# EveryCook_RaspiShield_V3.net
KiCad netlist of a schematic drawn in EAGLE
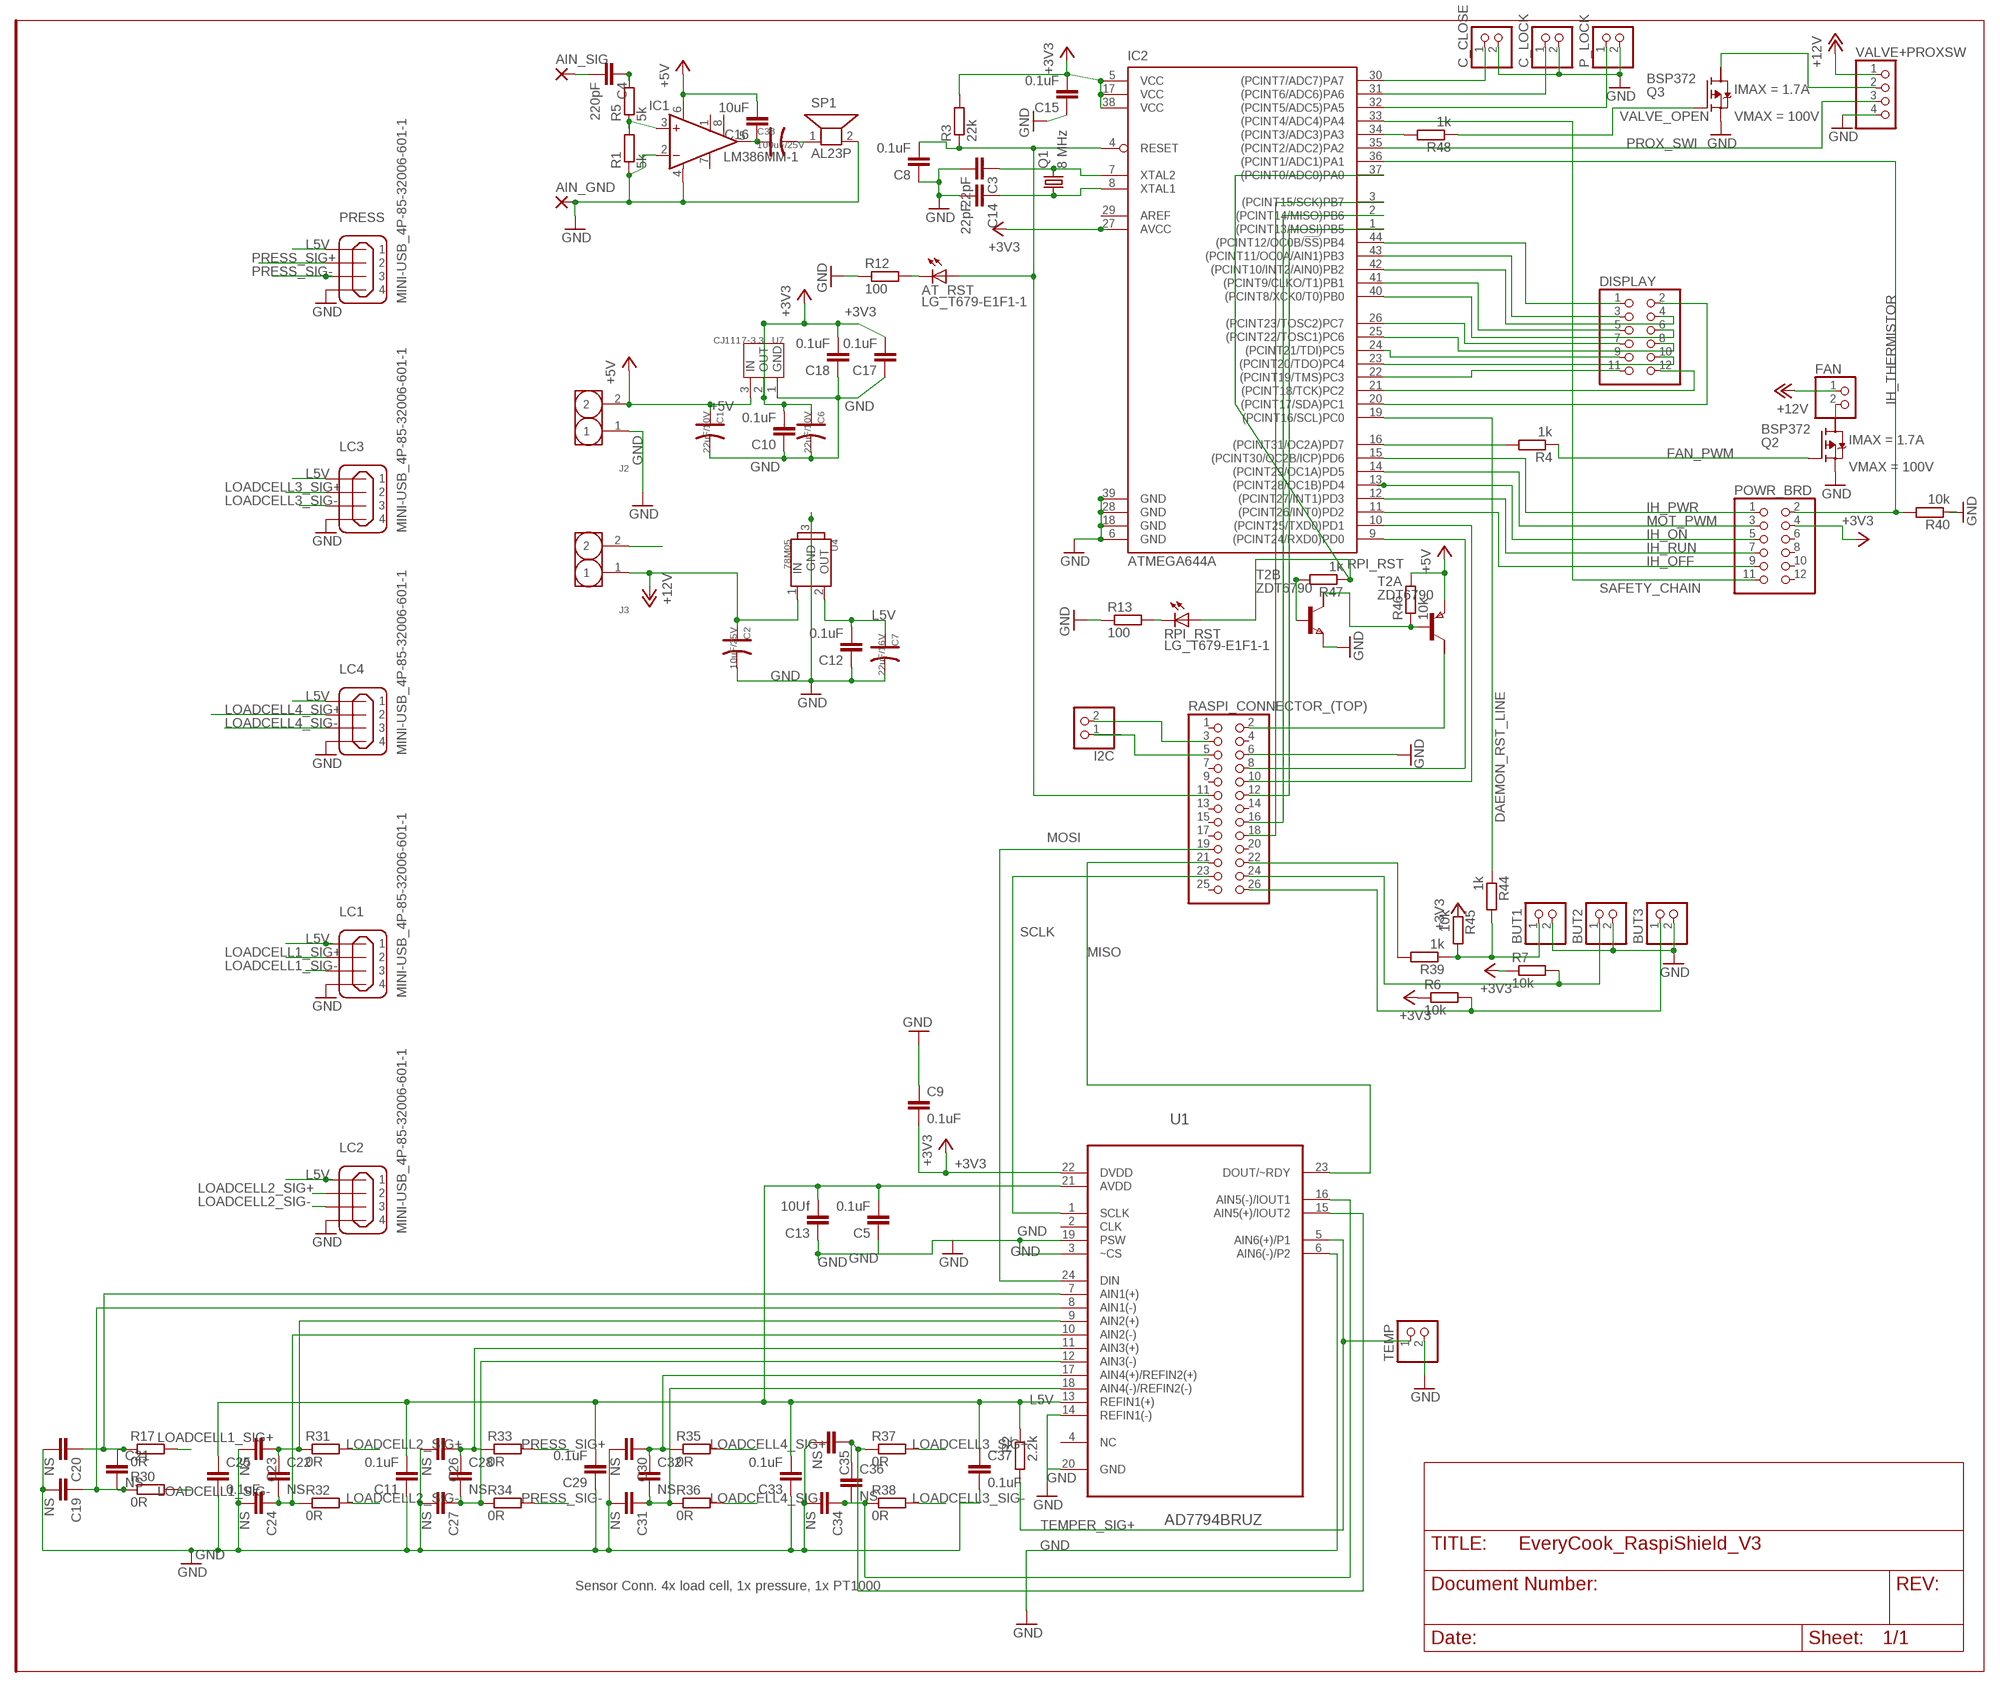
[diagram p0: schematic, sheet 1]

(export (version "E")
  (design (tool "Eeschema 10.0.6"))
  (components
    (comp (ref "AIN_GND")
      (value "2,15/1,0")
      (footprint "eagle-import:2,15_1,0")
      (libsource (lib "eagle-import") (part "2,15/1,0"))
    )
    (comp (ref "AIN_SIG")
      (value "2,15/1,0")
      (footprint "eagle-import:2,15_1,0")
      (libsource (lib "eagle-import") (part "2,15/1,0"))
    )
    (comp (ref "AT_RST")
      (value "LG_T679-E1F1-1")
      (footprint "eagle-import:PLCC2")
      (libsource (lib "eagle-import") (part "_T679-?-1E1F1LG"))
    )
    (comp (ref "BUT1")
      (value "PINHD-1X2")
      (footprint "eagle-import:1X02")
      (libsource (lib "eagle-import") (part "PINHD-1X2"))
    )
    (comp (ref "BUT2")
      (value "PINHD-1X2")
      (footprint "eagle-import:1X02")
      (libsource (lib "eagle-import") (part "PINHD-1X2"))
    )
    (comp (ref "BUT3")
      (value "PINHD-1X2")
      (footprint "eagle-import:1X02")
      (libsource (lib "eagle-import") (part "PINHD-1X2"))
    )
    (comp (ref "C1")
      (value "22uF/10V")
      (footprint "eagle-import:AVX-A")
      (libsource (lib "eagle-import") (part "CAP-AVX-A"))
    )
    (comp (ref "C2")
      (value "10uF/25V")
      (footprint "eagle-import:ELECTRO-SMD-B-4.8MM")
      (libsource (lib "eagle-import") (part "CAP-ELECTRO-B"))
    )
    (comp (ref "C3")
      (value "22pF")
      (footprint "eagle-import:C0805")
      (libsource (lib "eagle-import") (part "C-EUC0805"))
    )
    (comp (ref "C4")
      (value "220pF")
      (footprint "eagle-import:C0805")
      (libsource (lib "eagle-import") (part "C-EUC0805"))
    )
    (comp (ref "C5")
      (value "0.1uF")
      (footprint "eagle-import:C0805")
      (libsource (lib "eagle-import") (part "C-EUC0805"))
    )
    (comp (ref "C6")
      (value "22uF/10V")
      (footprint "eagle-import:AVX-A")
      (libsource (lib "eagle-import") (part "CAP-AVX-A"))
    )
    (comp (ref "C7")
      (value "22uF/16V")
      (footprint "eagle-import:ELECTRO-SMD-B-4.8MM")
      (libsource (lib "eagle-import") (part "CAP-ELECTRO-B"))
    )
    (comp (ref "C8")
      (value "0.1uF")
      (footprint "eagle-import:C0805")
      (libsource (lib "eagle-import") (part "C-EUC0805"))
    )
    (comp (ref "C9")
      (value "0.1uF")
      (footprint "eagle-import:C0805")
      (libsource (lib "eagle-import") (part "C-EUC0805"))
    )
    (comp (ref "C10")
      (value "0.1uF")
      (footprint "eagle-import:C0805")
      (libsource (lib "eagle-import") (part "C-EUC0805"))
    )
    (comp (ref "C11")
      (value "0.1uF")
      (footprint "eagle-import:C0805")
      (libsource (lib "eagle-import") (part "C-EUC0805"))
    )
    (comp (ref "C12")
      (value "0.1uF")
      (footprint "eagle-import:C0805")
      (libsource (lib "eagle-import") (part "C-EUC0805"))
    )
    (comp (ref "C13")
      (value "10Uf")
      (footprint "eagle-import:C0805")
      (libsource (lib "eagle-import") (part "C-EUC0805"))
    )
    (comp (ref "C14")
      (value "22pF")
      (footprint "eagle-import:C0805")
      (libsource (lib "eagle-import") (part "C-EUC0805"))
    )
    (comp (ref "C15")
      (value "0.1uF")
      (footprint "eagle-import:C0805")
      (libsource (lib "eagle-import") (part "C-EUC0805"))
    )
    (comp (ref "C16")
      (value "10uF")
      (footprint "eagle-import:C0805")
      (libsource (lib "eagle-import") (part "C-EUC0805"))
    )
    (comp (ref "C17")
      (value "0.1uF")
      (footprint "eagle-import:C0805")
      (libsource (lib "eagle-import") (part "C-EUC0805"))
    )
    (comp (ref "C18")
      (value "0.1uF")
      (footprint "eagle-import:C0805")
      (libsource (lib "eagle-import") (part "C-EUC0805"))
    )
    (comp (ref "C19")
      (value "NS")
      (footprint "eagle-import:C0805")
      (libsource (lib "eagle-import") (part "C-EUC0805"))
    )
    (comp (ref "C20")
      (value "NS")
      (footprint "eagle-import:C0805")
      (libsource (lib "eagle-import") (part "C-EUC0805"))
    )
    (comp (ref "C21")
      (value "NS")
      (footprint "eagle-import:C0805")
      (libsource (lib "eagle-import") (part "C-EUC0805"))
    )
    (comp (ref "C22")
      (value "NS")
      (footprint "eagle-import:C0805")
      (libsource (lib "eagle-import") (part "C-EUC0805"))
    )
    (comp (ref "C23")
      (value "NS")
      (footprint "eagle-import:C0805")
      (libsource (lib "eagle-import") (part "C-EUC0805"))
    )
    (comp (ref "C24")
      (value "NS")
      (footprint "eagle-import:C0805")
      (libsource (lib "eagle-import") (part "C-EUC0805"))
    )
    (comp (ref "C25")
      (value "0.1uF")
      (footprint "eagle-import:C0805")
      (libsource (lib "eagle-import") (part "C-EUC0805"))
    )
    (comp (ref "C26")
      (value "NS")
      (footprint "eagle-import:C0805")
      (libsource (lib "eagle-import") (part "C-EUC0805"))
    )
    (comp (ref "C27")
      (value "NS")
      (footprint "eagle-import:C0805")
      (libsource (lib "eagle-import") (part "C-EUC0805"))
    )
    (comp (ref "C28")
      (value "NS")
      (footprint "eagle-import:C0805")
      (libsource (lib "eagle-import") (part "C-EUC0805"))
    )
    (comp (ref "C29")
      (value "0.1uF")
      (footprint "eagle-import:C0805")
      (libsource (lib "eagle-import") (part "C-EUC0805"))
    )
    (comp (ref "C30")
      (value "NS")
      (footprint "eagle-import:C0805")
      (libsource (lib "eagle-import") (part "C-EUC0805"))
    )
    (comp (ref "C31")
      (value "NS")
      (footprint "eagle-import:C0805")
      (libsource (lib "eagle-import") (part "C-EUC0805"))
    )
    (comp (ref "C32")
      (value "NS")
      (footprint "eagle-import:C0805")
      (libsource (lib "eagle-import") (part "C-EUC0805"))
    )
    (comp (ref "C33")
      (value "0.1uF")
      (footprint "eagle-import:C0805")
      (libsource (lib "eagle-import") (part "C-EUC0805"))
    )
    (comp (ref "C34")
      (value "NS")
      (footprint "eagle-import:C0805")
      (libsource (lib "eagle-import") (part "C-EUC0805"))
    )
    (comp (ref "C35")
      (value "NS")
      (footprint "eagle-import:C0805")
      (libsource (lib "eagle-import") (part "C-EUC0805"))
    )
    (comp (ref "C36")
      (value "NS")
      (footprint "eagle-import:C0805")
      (libsource (lib "eagle-import") (part "C-EUC0805"))
    )
    (comp (ref "C37")
      (value "0.1uF")
      (footprint "eagle-import:C0805")
      (libsource (lib "eagle-import") (part "C-EUC0805"))
    )
    (comp (ref "C38")
      (value "100uF/25V")
      (footprint "eagle-import:ELECTRO-SMD-B-4.8MM")
      (libsource (lib "eagle-import") (part "CAP-ELECTRO-B"))
    )
    (comp (ref "C_CLOSE")
      (value "PINHD-1X2")
      (footprint "eagle-import:1X02")
      (libsource (lib "eagle-import") (part "PINHD-1X2"))
    )
    (comp (ref "C_LOCK")
      (value "PINHD-1X2")
      (footprint "eagle-import:1X02")
      (libsource (lib "eagle-import") (part "PINHD-1X2"))
    )
    (comp (ref "DISPLAY")
      (value "PINHD-2X6")
      (footprint "eagle-import:2X06")
      (libsource (lib "eagle-import") (part "PINHD-2X6"))
    )
    (comp (ref "FAN")
      (value "PINHD-1X2")
      (footprint "eagle-import:1X02")
      (libsource (lib "eagle-import") (part "PINHD-1X2"))
    )
    (comp (ref "I2C")
      (value "PINHD-1X2")
      (footprint "eagle-import:1X02")
      (libsource (lib "eagle-import") (part "PINHD-1X2"))
    )
    (comp (ref "IC1")
      (value "LM386MM-1")
      (footprint "eagle-import:MMSOP08")
      (libsource (lib "eagle-import") (part "LM386?-MM1"))
    )
    (comp (ref "IC2")
      (value "ATMEGA644A")
      (footprint "eagle-import:TQFP44")
      (fields (field (name "MPN") "ATMEGA644PV-10AU"))
      (libsource (lib "eagle-import") (part "ATMEGA644A"))
    )
    (comp (ref "J2")
      (value "HEADER-2P-5.0")
      (footprint "eagle-import:2P-5.0")
      (libsource (lib "eagle-import") (part "HEADER-2P-5.0"))
    )
    (comp (ref "J3")
      (value "HEADER-2P-5.0")
      (footprint "eagle-import:2P-5.0")
      (libsource (lib "eagle-import") (part "HEADER-2P-5.0"))
    )
    (comp (ref "LC1")
      (value "MINI-USB_4P-85-32006-601-1")
      (footprint "eagle-import:85-32006-601-1")
      (libsource (lib "eagle-import") (part "MINI-USB_4P-85-32006-601-1"))
    )
    (comp (ref "LC2")
      (value "MINI-USB_4P-85-32006-601-1")
      (footprint "eagle-import:85-32006-601-1")
      (libsource (lib "eagle-import") (part "MINI-USB_4P-85-32006-601-1"))
    )
    (comp (ref "LC3")
      (value "MINI-USB_4P-85-32006-601-1")
      (footprint "eagle-import:85-32006-601-1")
      (libsource (lib "eagle-import") (part "MINI-USB_4P-85-32006-601-1"))
    )
    (comp (ref "LC4")
      (value "MINI-USB_4P-85-32006-601-1")
      (footprint "eagle-import:85-32006-601-1")
      (libsource (lib "eagle-import") (part "MINI-USB_4P-85-32006-601-1"))
    )
    (comp (ref "POWR_BRD")
      (value "PINHD-2X6")
      (footprint "eagle-import:2X06")
      (libsource (lib "eagle-import") (part "PINHD-2X6"))
    )
    (comp (ref "PRESS")
      (value "MINI-USB_4P-85-32006-601-1")
      (footprint "eagle-import:85-32006-601-1")
      (libsource (lib "eagle-import") (part "MINI-USB_4P-85-32006-601-1"))
    )
    (comp (ref "P_LOCK")
      (value "PINHD-1X2")
      (footprint "eagle-import:1X02")
      (libsource (lib "eagle-import") (part "PINHD-1X2"))
    )
    (comp (ref "Q1")
      (value "8 MHz")
      (footprint "eagle-import:HC49UP")
      (libsource (lib "eagle-import") (part "CRYSTALHC49UP"))
    )
    (comp (ref "Q2")
      (value "BSP372")
      (footprint "eagle-import:PG-SOT-223")
      (fields (field (name "IMAX") "1.7A") (field (name "MF") "Infineon") (field (name "VMAX") "100V"))
      (libsource (lib "eagle-import") (part "BSP613P"))
    )
    (comp (ref "Q3")
      (value "BSP372")
      (footprint "eagle-import:PG-SOT-223")
      (fields (field (name "IMAX") "1.7A") (field (name "MF") "Infineon") (field (name "VMAX") "100V"))
      (libsource (lib "eagle-import") (part "BSP613P"))
    )
    (comp (ref "R1")
      (value "5k")
      (footprint "eagle-import:R0805")
      (libsource (lib "eagle-import") (part "R-EU_R0805"))
    )
    (comp (ref "R2")
      (value "2.2k")
      (footprint "eagle-import:R0805")
      (libsource (lib "eagle-import") (part "R-EU_R0805"))
    )
    (comp (ref "R3")
      (value "22k")
      (footprint "eagle-import:R0805")
      (libsource (lib "eagle-import") (part "R-EU_R0805"))
    )
    (comp (ref "R4")
      (value "1k")
      (footprint "eagle-import:R0805")
      (libsource (lib "eagle-import") (part "R-EU_R0805"))
    )
    (comp (ref "R5")
      (value "5k")
      (footprint "eagle-import:R0805")
      (libsource (lib "eagle-import") (part "R-EU_R0805"))
    )
    (comp (ref "R6")
      (value "10k")
      (footprint "eagle-import:R0805")
      (libsource (lib "eagle-import") (part "R-EU_R0805"))
    )
    (comp (ref "R7")
      (value "10k")
      (footprint "eagle-import:R0805")
      (libsource (lib "eagle-import") (part "R-EU_R0805"))
    )
    (comp (ref "R12")
      (value "100")
      (footprint "eagle-import:R0805")
      (libsource (lib "eagle-import") (part "R-EU_R0805"))
    )
    (comp (ref "R13")
      (value "100")
      (footprint "eagle-import:R0805")
      (libsource (lib "eagle-import") (part "R-EU_R0805"))
    )
    (comp (ref "R17")
      (value "0R")
      (footprint "eagle-import:R0805")
      (libsource (lib "eagle-import") (part "R-EU_R0805"))
    )
    (comp (ref "R30")
      (value "0R")
      (footprint "eagle-import:R0805")
      (libsource (lib "eagle-import") (part "R-EU_R0805"))
    )
    (comp (ref "R31")
      (value "0R")
      (footprint "eagle-import:R0805")
      (libsource (lib "eagle-import") (part "R-EU_R0805"))
    )
    (comp (ref "R32")
      (value "0R")
      (footprint "eagle-import:R0805")
      (libsource (lib "eagle-import") (part "R-EU_R0805"))
    )
    (comp (ref "R33")
      (value "0R")
      (footprint "eagle-import:R0805")
      (libsource (lib "eagle-import") (part "R-EU_R0805"))
    )
    (comp (ref "R34")
      (value "0R")
      (footprint "eagle-import:R0805")
      (libsource (lib "eagle-import") (part "R-EU_R0805"))
    )
    (comp (ref "R35")
      (value "0R")
      (footprint "eagle-import:R0805")
      (libsource (lib "eagle-import") (part "R-EU_R0805"))
    )
    (comp (ref "R36")
      (value "0R")
      (footprint "eagle-import:R0805")
      (libsource (lib "eagle-import") (part "R-EU_R0805"))
    )
    (comp (ref "R37")
      (value "0R")
      (footprint "eagle-import:R0805")
      (libsource (lib "eagle-import") (part "R-EU_R0805"))
    )
    (comp (ref "R38")
      (value "0R")
      (footprint "eagle-import:R0805")
      (libsource (lib "eagle-import") (part "R-EU_R0805"))
    )
    (comp (ref "R39")
      (value "1k")
      (footprint "eagle-import:R0805")
      (libsource (lib "eagle-import") (part "R-EU_R0805"))
    )
    (comp (ref "R40")
      (value "10k")
      (footprint "eagle-import:R0805")
      (libsource (lib "eagle-import") (part "R-EU_R0805"))
    )
    (comp (ref "R44")
      (value "1k")
      (footprint "eagle-import:R0805")
      (libsource (lib "eagle-import") (part "R-EU_R0805"))
    )
    (comp (ref "R45")
      (value "10k")
      (footprint "eagle-import:R0805")
      (libsource (lib "eagle-import") (part "R-EU_R0805"))
    )
    (comp (ref "R46")
      (value "10k")
      (footprint "eagle-import:R0805")
      (libsource (lib "eagle-import") (part "R-EU_R0805"))
    )
    (comp (ref "R47")
      (value "1k")
      (footprint "eagle-import:R0805")
      (libsource (lib "eagle-import") (part "R-EU_R0805"))
    )
    (comp (ref "R48")
      (value "1k")
      (footprint "eagle-import:R0805")
      (libsource (lib "eagle-import") (part "R-EU_R0805"))
    )
    (comp (ref "RASPI_CONNECTOR_(TOP)")
      (value "PINHD-2X13")
      (footprint "eagle-import:2X13")
      (libsource (lib "eagle-import") (part "PINHD-2X13"))
    )
    (comp (ref "RPI_RST")
      (value "LG_T679-E1F1-1")
      (footprint "eagle-import:PLCC2")
      (libsource (lib "eagle-import") (part "_T679-?-1E1F1LG"))
    )
    (comp (ref "SP1")
      (value "AL23P")
      (footprint "eagle-import:AL23P")
      (libsource (lib "eagle-import") (part "AL23P"))
    )
    (comp (ref "T2")
      (value "ZDT6790")
      (footprint "eagle-import:SM8")
      (libsource (lib "eagle-import") (part "NPN_PNPSM8"))
    )
    (comp (ref "TEMP")
      (value "PINHD-1X2")
      (footprint "eagle-import:1X02")
      (libsource (lib "eagle-import") (part "PINHD-1X2"))
    )
    (comp (ref "U1")
      (value "AD7794BRUZ")
      (footprint "eagle-import:SOP65P640X120-24N")
      (libsource (lib "eagle-import") (part "AD7794BRUZ"))
    )
    (comp (ref "U4")
      (value "78M05")
      (footprint "eagle-import:TO252")
      (libsource (lib "eagle-import") (part "78M05-TO252"))
    )
    (comp (ref "U7")
      (value "CJ1117-3.3")
      (footprint "eagle-import:SOT89")
      (libsource (lib "eagle-import") (part "LD1117SOT89"))
    )
    (comp (ref "VALVE+PROXSW")
      (value "PINHD-1X4")
      (footprint "eagle-import:1X04")
      (libsource (lib "eagle-import") (part "PINHD-1X4"))
    )
  )
  (nets
    (net (code "1") (name "+3V3") (class "Default")
      (node (ref "C10") (pin "2") (pinfunction "2_2") (pintype "passive"))
      (node (ref "C15") (pin "2") (pinfunction "2_2") (pintype "passive"))
      (node (ref "C17") (pin "2") (pinfunction "2_2") (pintype "passive"))
      (node (ref "C18") (pin "2") (pinfunction "2_2") (pintype "passive"))
      (node (ref "C6") (pin "+") (pinfunction "+_+") (pintype "passive"))
      (node (ref "C9") (pin "2") (pinfunction "2_2") (pintype "passive"))
      (node (ref "IC2") (pin "17") (pinfunction "VCC_17") (pintype "power_in"))
      (node (ref "IC2") (pin "27") (pinfunction "AVCC_27") (pintype "power_in"))
      (node (ref "IC2") (pin "38") (pinfunction "VCC_38") (pintype "power_in"))
      (node (ref "IC2") (pin "5") (pinfunction "VCC_5") (pintype "power_in"))
      (node (ref "POWR_BRD") (pin "4") (pinfunction "4_4") (pintype "passive"))
      (node (ref "R3") (pin "2") (pinfunction "2_2") (pintype "passive"))
      (node (ref "R45") (pin "1") (pinfunction "1_1") (pintype "passive"))
      (node (ref "R6") (pin "1") (pinfunction "1_1") (pintype "passive"))
      (node (ref "R7") (pin "1") (pinfunction "1_1") (pintype "passive"))
      (node (ref "U1") (pin "22") (pinfunction "DVDD_22") (pintype "power_in"))
      (node (ref "U7") (pin "2") (pinfunction "OUT_2") (pintype "bidirectional"))
      (node (ref "U7") (pin "4") (pinfunction "TAB_4") (pintype "bidirectional"))
    )
    (net (code "2") (name "+5V") (class "Default")
      (node (ref "C1") (pin "+") (pinfunction "+_+") (pintype "passive"))
      (node (ref "C16") (pin "2") (pinfunction "2_2") (pintype "passive"))
      (node (ref "IC1") (pin "6") (pinfunction "VS_6") (pintype "power_in"))
      (node (ref "J2") (pin "2") (pinfunction "2_2") (pintype "bidirectional"))
      (node (ref "R46") (pin "2") (pinfunction "2_2") (pintype "passive"))
      (node (ref "T2") (pin "1") (pinfunction "E_1") (pintype "passive"))
      (node (ref "U7") (pin "3") (pinfunction "IN_3") (pintype "bidirectional"))
    )
    (net (code "3") (name "+12V") (class "Default")
      (node (ref "C2") (pin "+") (pinfunction "+_+") (pintype "passive"))
      (node (ref "FAN") (pin "1") (pinfunction "1_1") (pintype "passive"))
      (node (ref "J3") (pin "1") (pinfunction "1_1") (pintype "bidirectional"))
      (node (ref "U4") (pin "1") (pinfunction "IN_1") (pintype "bidirectional"))
      (node (ref "VALVE+PROXSW") (pin "1") (pinfunction "1_1") (pintype "passive"))
    )
    (net (code "4") (name "/DAEMON_RST_LINE") (class "Default")
      (node (ref "IC2") (pin "19") (pinfunction "(PCINT16/SCL)PC0_19") (pintype "output"))
      (node (ref "R44") (pin "1") (pinfunction "1_1") (pintype "passive"))
    )
    (net (code "5") (name "/FAN_PWM") (class "Default")
      (node (ref "Q2") (pin "1") (pinfunction "G_1") (pintype "passive"))
      (node (ref "R4") (pin "1") (pinfunction "1_1") (pintype "passive"))
    )
    (net (code "6") (name "/IH_OFF") (class "Default")
      (node (ref "IC2") (pin "11") (pinfunction "(PCINT26/INT0)PD2_11") (pintype "bidirectional"))
      (node (ref "POWR_BRD") (pin "9") (pinfunction "9_9") (pintype "passive"))
    )
    (net (code "7") (name "/IH_ON") (class "Default")
      (node (ref "IC2") (pin "13") (pinfunction "(PCINT28/OC1B)PD4_13") (pintype "bidirectional"))
      (node (ref "POWR_BRD") (pin "5") (pinfunction "5_5") (pintype "passive"))
    )
    (net (code "8") (name "/IH_PWR") (class "Default")
      (node (ref "IC2") (pin "15") (pinfunction "(PCINT30/OC2B/ICP)PD6_15") (pintype "bidirectional"))
      (node (ref "POWR_BRD") (pin "1") (pinfunction "1_1") (pintype "passive"))
    )
    (net (code "9") (name "/IH_RUN") (class "Default")
      (node (ref "IC2") (pin "12") (pinfunction "(PCINT27/INT1)PD3_12") (pintype "bidirectional"))
      (node (ref "POWR_BRD") (pin "7") (pinfunction "7_7") (pintype "passive"))
    )
    (net (code "10") (name "/IH_THERMISTOR") (class "Default")
      (node (ref "IC2") (pin "36") (pinfunction "(PCINT1/ADC1)PA1_36") (pintype "bidirectional"))
      (node (ref "POWR_BRD") (pin "2") (pinfunction "2_2") (pintype "passive"))
      (node (ref "R40") (pin "2") (pinfunction "2_2") (pintype "passive"))
    )
    (net (code "11") (name "/L5V") (class "Default")
      (node (ref "C11") (pin "2") (pinfunction "2_2") (pintype "passive"))
      (node (ref "C12") (pin "2") (pinfunction "2_2") (pintype "passive"))
      (node (ref "C13") (pin "2") (pinfunction "2_2") (pintype "passive"))
      (node (ref "C25") (pin "1") (pinfunction "1_1") (pintype "passive"))
      (node (ref "C29") (pin "2") (pinfunction "2_2") (pintype "passive"))
      (node (ref "C33") (pin "2") (pinfunction "2_2") (pintype "passive"))
      (node (ref "C37") (pin "1") (pinfunction "1_1") (pintype "passive"))
      (node (ref "C5") (pin "2") (pinfunction "2_2") (pintype "passive"))
      (node (ref "C7") (pin "+") (pinfunction "+_+") (pintype "passive"))
      (node (ref "LC1") (pin "1") (pinfunction "1_1") (pintype "passive"))
      (node (ref "LC2") (pin "1") (pinfunction "1_1") (pintype "passive"))
      (node (ref "LC3") (pin "1") (pinfunction "1_1") (pintype "passive"))
      (node (ref "LC4") (pin "1") (pinfunction "1_1") (pintype "passive"))
      (node (ref "PRESS") (pin "1") (pinfunction "1_1") (pintype "passive"))
      (node (ref "R2") (pin "1") (pinfunction "1_1") (pintype "passive"))
      (node (ref "U1") (pin "13") (pinfunction "REFIN1(+)_13") (pintype "input"))
      (node (ref "U1") (pin "21") (pinfunction "AVDD_21") (pintype "power_in"))
      (node (ref "U4") (pin "2") (pinfunction "OUT_2") (pintype "bidirectional"))
    )
    (net (code "12") (name "/LOADCELL1_SIG+") (class "Default")
      (node (ref "LC1") (pin "2") (pinfunction "2_2") (pintype "passive"))
      (node (ref "R17") (pin "2") (pinfunction "2_2") (pintype "passive"))
    )
    (net (code "13") (name "/LOADCELL1_SIG-") (class "Default")
      (node (ref "LC1") (pin "3") (pinfunction "3_3") (pintype "passive"))
      (node (ref "R30") (pin "2") (pinfunction "2_2") (pintype "passive"))
    )
    (net (code "14") (name "/LOADCELL2_SIG+") (class "Default")
      (node (ref "LC2") (pin "2") (pinfunction "2_2") (pintype "passive"))
      (node (ref "R31") (pin "2") (pinfunction "2_2") (pintype "passive"))
    )
    (net (code "15") (name "/LOADCELL2_SIG-") (class "Default")
      (node (ref "LC2") (pin "3") (pinfunction "3_3") (pintype "passive"))
      (node (ref "R32") (pin "2") (pinfunction "2_2") (pintype "passive"))
    )
    (net (code "16") (name "/LOADCELL3_SIG+") (class "Default")
      (node (ref "LC3") (pin "2") (pinfunction "2_2") (pintype "passive"))
      (node (ref "R37") (pin "2") (pinfunction "2_2") (pintype "passive"))
    )
    (net (code "17") (name "/LOADCELL3_SIG-") (class "Default")
      (node (ref "LC3") (pin "3") (pinfunction "3_3") (pintype "passive"))
      (node (ref "R38") (pin "2") (pinfunction "2_2") (pintype "passive"))
    )
    (net (code "18") (name "/LOADCELL4_SIG+") (class "Default")
      (node (ref "LC4") (pin "2") (pinfunction "2_2") (pintype "passive"))
      (node (ref "R35") (pin "2") (pinfunction "2_2") (pintype "passive"))
    )
    (net (code "19") (name "/LOADCELL4_SIG-") (class "Default")
      (node (ref "LC4") (pin "3") (pinfunction "3_3") (pintype "passive"))
      (node (ref "R36") (pin "2") (pinfunction "2_2") (pintype "passive"))
    )
    (net (code "20") (name "/MISO") (class "Default")
      (node (ref "RASPI_CONNECTOR_(TOP)") (pin "21") (pinfunction "21_21") (pintype "passive"))
      (node (ref "U1") (pin "23") (pinfunction "DOUT/~{RDY}_23") (pintype "bidirectional"))
    )
    (net (code "21") (name "/MOSI") (class "Default")
      (node (ref "RASPI_CONNECTOR_(TOP)") (pin "19") (pinfunction "19_19") (pintype "passive"))
      (node (ref "U1") (pin "24") (pinfunction "DIN_24") (pintype "input"))
    )
    (net (code "22") (name "/MOT_PWM") (class "Default")
      (node (ref "IC2") (pin "14") (pinfunction "(PCINT29/OC1A)PD5_14") (pintype "bidirectional"))
      (node (ref "POWR_BRD") (pin "3") (pinfunction "3_3") (pintype "passive"))
    )
    (net (code "23") (name "/PRESS_SIG+") (class "Default")
      (node (ref "PRESS") (pin "2") (pinfunction "2_2") (pintype "passive"))
      (node (ref "R33") (pin "2") (pinfunction "2_2") (pintype "passive"))
    )
    (net (code "24") (name "/PRESS_SIG-") (class "Default")
      (node (ref "PRESS") (pin "3") (pinfunction "3_3") (pintype "passive"))
      (node (ref "R34") (pin "2") (pinfunction "2_2") (pintype "passive"))
    )
    (net (code "25") (name "/PROX_SWI") (class "Default")
      (node (ref "IC2") (pin "35") (pinfunction "(PCINT2/ADC2)PA2_35") (pintype "bidirectional"))
      (node (ref "VALVE+PROXSW") (pin "3") (pinfunction "3_3") (pintype "passive"))
    )
    (net (code "26") (name "/RPI_RST") (class "Default")
      (node (ref "IC2") (pin "37") (pinfunction "(PCINT0/ADC0)PA0_37") (pintype "bidirectional"))
      (node (ref "R47") (pin "1") (pinfunction "1_1") (pintype "passive"))
      (node (ref "RPI_RST") (pin "A") (pinfunction "A_A") (pintype "passive"))
    )
    (net (code "27") (name "/SAFETY_CHAIN") (class "Default")
      (node (ref "IC2") (pin "33") (pinfunction "(PCINT4/ADC4)PA4_33") (pintype "bidirectional"))
      (node (ref "POWR_BRD") (pin "11") (pinfunction "11_11") (pintype "passive"))
    )
    (net (code "28") (name "/SCLK") (class "Default")
      (node (ref "RASPI_CONNECTOR_(TOP)") (pin "23") (pinfunction "23_23") (pintype "passive"))
      (node (ref "U1") (pin "1") (pinfunction "SCLK_1") (pintype "input"))
    )
    (net (code "29") (name "/TEMPER_SIG+") (class "Default")
      (node (ref "R2") (pin "2") (pinfunction "2_2") (pintype "passive"))
      (node (ref "TEMP") (pin "1") (pinfunction "1_1") (pintype "passive"))
      (node (ref "U1") (pin "5") (pinfunction "AIN6(+)/P1_5") (pintype "bidirectional"))
    )
    (net (code "30") (name "/VALVE_OPEN") (class "Default")
      (node (ref "Q3") (pin "1") (pinfunction "G_1") (pintype "passive"))
      (node (ref "R48") (pin "1") (pinfunction "1_1") (pintype "passive"))
    )
    (net (code "31") (name "GND") (class "Default")
      (node (ref "AIN_GND") (pin "1") (pinfunction "P_1") (pintype "passive"))
      (node (ref "BUT1") (pin "2") (pinfunction "2_2") (pintype "passive"))
      (node (ref "BUT2") (pin "2") (pinfunction "2_2") (pintype "passive"))
      (node (ref "BUT3") (pin "2") (pinfunction "2_2") (pintype "passive"))
      (node (ref "C1") (pin "-") (pinfunction "-_-") (pintype "passive"))
      (node (ref "C10") (pin "1") (pinfunction "1_1") (pintype "passive"))
      (node (ref "C11") (pin "1") (pinfunction "1_1") (pintype "passive"))
      (node (ref "C12") (pin "1") (pinfunction "1_1") (pintype "passive"))
      (node (ref "C13") (pin "1") (pinfunction "1_1") (pintype "passive"))
      (node (ref "C14") (pin "2") (pinfunction "2_2") (pintype "passive"))
      (node (ref "C15") (pin "1") (pinfunction "1_1") (pintype "passive"))
      (node (ref "C17") (pin "1") (pinfunction "1_1") (pintype "passive"))
      (node (ref "C18") (pin "1") (pinfunction "1_1") (pintype "passive"))
      (node (ref "C19") (pin "2") (pinfunction "2_2") (pintype "passive"))
      (node (ref "C2") (pin "-") (pinfunction "-_-") (pintype "passive"))
      (node (ref "C20") (pin "2") (pinfunction "2_2") (pintype "passive"))
      (node (ref "C23") (pin "2") (pinfunction "2_2") (pintype "passive"))
      (node (ref "C24") (pin "2") (pinfunction "2_2") (pintype "passive"))
      (node (ref "C25") (pin "2") (pinfunction "2_2") (pintype "passive"))
      (node (ref "C26") (pin "2") (pinfunction "2_2") (pintype "passive"))
      (node (ref "C27") (pin "2") (pinfunction "2_2") (pintype "passive"))
      (node (ref "C29") (pin "1") (pinfunction "1_1") (pintype "passive"))
      (node (ref "C3") (pin "2") (pinfunction "2_2") (pintype "passive"))
      (node (ref "C30") (pin "2") (pinfunction "2_2") (pintype "passive"))
      (node (ref "C31") (pin "2") (pinfunction "2_2") (pintype "passive"))
      (node (ref "C33") (pin "1") (pinfunction "1_1") (pintype "passive"))
      (node (ref "C34") (pin "2") (pinfunction "2_2") (pintype "passive"))
      (node (ref "C35") (pin "2") (pinfunction "2_2") (pintype "passive"))
      (node (ref "C37") (pin "2") (pinfunction "2_2") (pintype "passive"))
      (node (ref "C5") (pin "1") (pinfunction "1_1") (pintype "passive"))
      (node (ref "C6") (pin "-") (pinfunction "-_-") (pintype "passive"))
      (node (ref "C7") (pin "-") (pinfunction "-_-") (pintype "passive"))
      (node (ref "C8") (pin "1") (pinfunction "1_1") (pintype "passive"))
      (node (ref "C9") (pin "1") (pinfunction "1_1") (pintype "passive"))
      (node (ref "C_CLOSE") (pin "2") (pinfunction "2_2") (pintype "passive"))
      (node (ref "C_LOCK") (pin "2") (pinfunction "2_2") (pintype "passive"))
      (node (ref "IC1") (pin "2") (pinfunction "-IN_2") (pintype "input"))
      (node (ref "IC1") (pin "4") (pinfunction "GND_4") (pintype "power_in"))
      (node (ref "IC2") (pin "18") (pinfunction "GND_18") (pintype "power_in"))
      (node (ref "IC2") (pin "28") (pinfunction "GND_28") (pintype "power_in"))
      (node (ref "IC2") (pin "39") (pinfunction "GND_39") (pintype "power_in"))
      (node (ref "IC2") (pin "6") (pinfunction "GND_6") (pintype "power_in"))
      (node (ref "J2") (pin "1") (pinfunction "1_1") (pintype "bidirectional"))
      (node (ref "LC1") (pin "4") (pinfunction "4_4") (pintype "passive"))
      (node (ref "LC2") (pin "4") (pinfunction "4_4") (pintype "passive"))
      (node (ref "LC3") (pin "4") (pinfunction "4_4") (pintype "passive"))
      (node (ref "LC4") (pin "4") (pinfunction "4_4") (pintype "passive"))
      (node (ref "PRESS") (pin "4") (pinfunction "4_4") (pintype "passive"))
      (node (ref "P_LOCK") (pin "2") (pinfunction "2_2") (pintype "passive"))
      (node (ref "Q2") (pin "3") (pinfunction "S_3") (pintype "passive"))
      (node (ref "Q3") (pin "3") (pinfunction "S_3") (pintype "passive"))
      (node (ref "R1") (pin "1") (pinfunction "1_1") (pintype "passive"))
      (node (ref "R12") (pin "1") (pinfunction "1_1") (pintype "passive"))
      (node (ref "R13") (pin "1") (pinfunction "1_1") (pintype "passive"))
      (node (ref "R40") (pin "1") (pinfunction "1_1") (pintype "passive"))
      (node (ref "RASPI_CONNECTOR_(TOP)") (pin "6") (pinfunction "6_6") (pintype "passive"))
      (node (ref "SP1") (pin "2") (pinfunction "2_2") (pintype "passive"))
      (node (ref "T2") (pin "3") (pinfunction "E_3") (pintype "passive"))
      (node (ref "TEMP") (pin "2") (pinfunction "2_2") (pintype "passive"))
      (node (ref "U1") (pin "14") (pinfunction "REFIN1(-)_14") (pintype "input"))
      (node (ref "U1") (pin "19") (pinfunction "PSW_19") (pintype "passive"))
      (node (ref "U1") (pin "20") (pinfunction "GND_20") (pintype "passive"))
      (node (ref "U1") (pin "3") (pinfunction "~{CS}_3") (pintype "input"))
      (node (ref "U1") (pin "6") (pinfunction "AIN6(-)/P2_6") (pintype "bidirectional"))
      (node (ref "U4") (pin "3") (pinfunction "GND_3") (pintype "bidirectional"))
      (node (ref "U7") (pin "1") (pinfunction "GND_1") (pintype "bidirectional"))
      (node (ref "VALVE+PROXSW") (pin "4") (pinfunction "4_4") (pintype "passive"))
    )
    (net (code "32") (name "Net-(AIN_SIG-P)") (class "Default")
      (node (ref "AIN_SIG") (pin "1") (pinfunction "P_1") (pintype "passive"))
      (node (ref "C4") (pin "2") (pinfunction "2_2") (pintype "passive"))
    )
    (net (code "33") (name "Net-(AT_RST-PadC)") (class "Default")
      (node (ref "AT_RST") (pin "C") (pinfunction "C_C") (pintype "passive"))
      (node (ref "R12") (pin "2") (pinfunction "2_2") (pintype "passive"))
    )
    (net (code "34") (name "Net-(BUT1-Pad1)") (class "Default")
      (node (ref "BUT1") (pin "1") (pinfunction "1_1") (pintype "passive"))
      (node (ref "R39") (pin "1") (pinfunction "1_1") (pintype "passive"))
      (node (ref "R44") (pin "2") (pinfunction "2_2") (pintype "passive"))
      (node (ref "R45") (pin "2") (pinfunction "2_2") (pintype "passive"))
    )
    (net (code "35") (name "Net-(BUT2-Pad1)") (class "Default")
      (node (ref "BUT2") (pin "1") (pinfunction "1_1") (pintype "passive"))
      (node (ref "R7") (pin "2") (pinfunction "2_2") (pintype "passive"))
      (node (ref "RASPI_CONNECTOR_(TOP)") (pin "24") (pinfunction "24_24") (pintype "passive"))
    )
    (net (code "36") (name "Net-(BUT3-Pad1)") (class "Default")
      (node (ref "BUT3") (pin "1") (pinfunction "1_1") (pintype "passive"))
      (node (ref "R6") (pin "2") (pinfunction "2_2") (pintype "passive"))
      (node (ref "RASPI_CONNECTOR_(TOP)") (pin "26") (pinfunction "26_26") (pintype "passive"))
    )
    (net (code "37") (name "Net-(C4-Pad1)") (class "Default")
      (node (ref "C4") (pin "1") (pinfunction "1_1") (pintype "passive"))
      (node (ref "R5") (pin "2") (pinfunction "2_2") (pintype "passive"))
    )
    (net (code "38") (name "Net-(C38-Pad-)") (class "Default")
      (node (ref "C38") (pin "-") (pinfunction "-_-") (pintype "passive"))
      (node (ref "SP1") (pin "1") (pinfunction "1_1") (pintype "passive"))
    )
    (net (code "39") (name "Net-(FAN-Pad2)") (class "Default")
      (node (ref "FAN") (pin "2") (pinfunction "2_2") (pintype "passive"))
      (node (ref "Q2") (pin "2") (pinfunction "D_2") (pintype "passive"))
    )
    (net (code "40") (name "Net-(I2C-Pad1)") (class "Default")
      (node (ref "I2C") (pin "1") (pinfunction "1_1") (pintype "passive"))
      (node (ref "RASPI_CONNECTOR_(TOP)") (pin "5") (pinfunction "5_5") (pintype "passive"))
    )
    (net (code "41") (name "Net-(I2C-Pad2)") (class "Default")
      (node (ref "I2C") (pin "2") (pinfunction "2_2") (pintype "passive"))
      (node (ref "RASPI_CONNECTOR_(TOP)") (pin "3") (pinfunction "3_3") (pintype "passive"))
    )
    (net (code "42") (name "Net-(IC1-+IN)") (class "Default")
      (node (ref "IC1") (pin "3") (pinfunction "+IN_3") (pintype "input"))
      (node (ref "R1") (pin "2") (pinfunction "2_2") (pintype "passive"))
      (node (ref "R5") (pin "1") (pinfunction "1_1") (pintype "passive"))
    )
    (net (code "43") (name "Net-(IC1-OUT)") (class "Default")
      (node (ref "C16") (pin "1") (pinfunction "1_1") (pintype "passive"))
      (node (ref "C38") (pin "+") (pinfunction "+_+") (pintype "passive"))
      (node (ref "IC1") (pin "5") (pinfunction "OUT_5") (pintype "output"))
    )
    (net (code "44") (name "Net-(IC2-(PCINT3{slash}ADC3)PA3)") (class "Default")
      (node (ref "IC2") (pin "34") (pinfunction "(PCINT3/ADC3)PA3_34") (pintype "bidirectional"))
      (node (ref "R48") (pin "2") (pinfunction "2_2") (pintype "passive"))
    )
    (net (code "45") (name "Net-(IC2-(PCINT5{slash}ADC5)PA5)") (class "Default")
      (node (ref "IC2") (pin "32") (pinfunction "(PCINT5/ADC5)PA5_32") (pintype "bidirectional"))
      (node (ref "P_LOCK") (pin "1") (pinfunction "1_1") (pintype "passive"))
    )
    (net (code "46") (name "Net-(IC2-(PCINT6{slash}ADC6)PA6)") (class "Default")
      (node (ref "C_LOCK") (pin "1") (pinfunction "1_1") (pintype "passive"))
      (node (ref "IC2") (pin "31") (pinfunction "(PCINT6/ADC6)PA6_31") (pintype "bidirectional"))
    )
    (net (code "47") (name "Net-(IC2-(PCINT7{slash}ADC7)PA7)") (class "Default")
      (node (ref "C_CLOSE") (pin "1") (pinfunction "1_1") (pintype "passive"))
      (node (ref "IC2") (pin "30") (pinfunction "(PCINT7/ADC7)PA7_30") (pintype "bidirectional"))
    )
    (net (code "48") (name "Net-(IC2-(PCINT8{slash}XCK0{slash}T0)PB0)") (class "Default")
      (node (ref "DISPLAY") (pin "6") (pinfunction "6_6") (pintype "passive"))
      (node (ref "IC2") (pin "40") (pinfunction "(PCINT8/XCK0/T0)PB0_40") (pintype "bidirectional"))
    )
    (net (code "49") (name "Net-(IC2-(PCINT9{slash}CLKO{slash}T1)PB1)") (class "Default")
      (node (ref "DISPLAY") (pin "5") (pinfunction "5_5") (pintype "passive"))
      (node (ref "IC2") (pin "41") (pinfunction "(PCINT9/CLKO/T1)PB1_41") (pintype "bidirectional"))
    )
    (net (code "50") (name "Net-(IC2-(PCINT10{slash}INT2{slash}AIN0)PB2)") (class "Default")
      (node (ref "DISPLAY") (pin "4") (pinfunction "4_4") (pintype "passive"))
      (node (ref "IC2") (pin "42") (pinfunction "(PCINT10/INT2/AIN0)PB2_42") (pintype "bidirectional"))
    )
    (net (code "51") (name "Net-(IC2-(PCINT11{slash}OC0A{slash}AIN1)PB3)") (class "Default")
      (node (ref "DISPLAY") (pin "3") (pinfunction "3_3") (pintype "passive"))
      (node (ref "IC2") (pin "43") (pinfunction "(PCINT11/OC0A/AIN1)PB3_43") (pintype "bidirectional"))
    )
    (net (code "52") (name "Net-(IC2-(PCINT12{slash}OC0B{slash}~{SS})PB4)") (class "Default")
      (node (ref "DISPLAY") (pin "1") (pinfunction "1_1") (pintype "passive"))
      (node (ref "IC2") (pin "44") (pinfunction "(PCINT12/OC0B/~{SS})PB4_44") (pintype "bidirectional"))
    )
    (net (code "53") (name "Net-(IC2-(PCINT13{slash}MOSI)PB5)") (class "Default")
      (node (ref "IC2") (pin "1") (pinfunction "(PCINT13/MOSI)PB5_1") (pintype "bidirectional"))
      (node (ref "RASPI_CONNECTOR_(TOP)") (pin "12") (pinfunction "12_12") (pintype "passive"))
    )
    (net (code "54") (name "Net-(IC2-(PCINT14{slash}MISO)PB6)") (class "Default")
      (node (ref "IC2") (pin "2") (pinfunction "(PCINT14/MISO)PB6_2") (pintype "bidirectional"))
      (node (ref "RASPI_CONNECTOR_(TOP)") (pin "16") (pinfunction "16_16") (pintype "passive"))
    )
    (net (code "55") (name "Net-(IC2-(PCINT15{slash}SCK)PB7)") (class "Default")
      (node (ref "IC2") (pin "3") (pinfunction "(PCINT15/SCK)PB7_3") (pintype "bidirectional"))
      (node (ref "RASPI_CONNECTOR_(TOP)") (pin "18") (pinfunction "18_18") (pintype "passive"))
    )
    (net (code "56") (name "Net-(IC2-(PCINT17{slash}SDA)PC1)") (class "Default")
      (node (ref "DISPLAY") (pin "2") (pinfunction "2_2") (pintype "passive"))
      (node (ref "IC2") (pin "20") (pinfunction "(PCINT17/SDA)PC1_20") (pintype "output"))
    )
    (net (code "57") (name "Net-(IC2-(PCINT18{slash}TCK)PC2)") (class "Default")
      (node (ref "DISPLAY") (pin "12") (pinfunction "12_12") (pintype "passive"))
      (node (ref "IC2") (pin "21") (pinfunction "(PCINT18/TCK)PC2_21") (pintype "output"))
    )
    (net (code "58") (name "Net-(IC2-(PCINT19{slash}TMS)PC3)") (class "Default")
      (node (ref "DISPLAY") (pin "11") (pinfunction "11_11") (pintype "passive"))
      (node (ref "IC2") (pin "22") (pinfunction "(PCINT19/TMS)PC3_22") (pintype "output"))
    )
    (net (code "59") (name "Net-(IC2-(PCINT20{slash}TDO)PC4)") (class "Default")
      (node (ref "DISPLAY") (pin "10") (pinfunction "10_10") (pintype "passive"))
      (node (ref "IC2") (pin "23") (pinfunction "(PCINT20/TDO)PC4_23") (pintype "output"))
    )
    (net (code "60") (name "Net-(IC2-(PCINT21{slash}TDI)PC5)") (class "Default")
      (node (ref "DISPLAY") (pin "9") (pinfunction "9_9") (pintype "passive"))
      (node (ref "IC2") (pin "24") (pinfunction "(PCINT21/TDI)PC5_24") (pintype "output"))
    )
    (net (code "61") (name "Net-(IC2-(PCINT22{slash}TOSC1)PC6)") (class "Default")
      (node (ref "DISPLAY") (pin "8") (pinfunction "8_8") (pintype "passive"))
      (node (ref "IC2") (pin "25") (pinfunction "(PCINT22/TOSC1)PC6_25") (pintype "output"))
    )
    (net (code "62") (name "Net-(IC2-(PCINT23{slash}TOSC2)PC7)") (class "Default")
      (node (ref "DISPLAY") (pin "7") (pinfunction "7_7") (pintype "passive"))
      (node (ref "IC2") (pin "26") (pinfunction "(PCINT23/TOSC2)PC7_26") (pintype "output"))
    )
    (net (code "63") (name "Net-(IC2-(PCINT24{slash}RXD0)PD0)") (class "Default")
      (node (ref "IC2") (pin "9") (pinfunction "(PCINT24/RXD0)PD0_9") (pintype "bidirectional"))
      (node (ref "RASPI_CONNECTOR_(TOP)") (pin "8") (pinfunction "8_8") (pintype "passive"))
    )
    (net (code "64") (name "Net-(IC2-(PCINT25{slash}TXD0)PD1)") (class "Default")
      (node (ref "IC2") (pin "10") (pinfunction "(PCINT25/TXD0)PD1_10") (pintype "bidirectional"))
      (node (ref "RASPI_CONNECTOR_(TOP)") (pin "10") (pinfunction "10_10") (pintype "passive"))
    )
    (net (code "65") (name "Net-(IC2-(PCINT31{slash}OC2A)PD7)") (class "Default")
      (node (ref "IC2") (pin "16") (pinfunction "(PCINT31/OC2A)PD7_16") (pintype "bidirectional"))
      (node (ref "R4") (pin "2") (pinfunction "2_2") (pintype "passive"))
    )
    (net (code "66") (name "Net-(IC2-RESET)") (class "Default")
      (node (ref "AT_RST") (pin "A") (pinfunction "A_A") (pintype "passive"))
      (node (ref "C8") (pin "2") (pinfunction "2_2") (pintype "passive"))
      (node (ref "IC2") (pin "4") (pinfunction "RESET_4") (pintype "input"))
      (node (ref "R3") (pin "1") (pinfunction "1_1") (pintype "passive"))
      (node (ref "RASPI_CONNECTOR_(TOP)") (pin "11") (pinfunction "11_11") (pintype "passive"))
    )
    (net (code "67") (name "Net-(IC2-XTAL1)") (class "Default")
      (node (ref "C14") (pin "1") (pinfunction "1_1") (pintype "passive"))
      (node (ref "IC2") (pin "8") (pinfunction "XTAL1_8") (pintype "bidirectional"))
      (node (ref "Q1") (pin "1") (pinfunction "1_1") (pintype "passive"))
    )
    (net (code "68") (name "Net-(IC2-XTAL2)") (class "Default")
      (node (ref "C3") (pin "1") (pinfunction "1_1") (pintype "passive"))
      (node (ref "IC2") (pin "7") (pinfunction "XTAL2_7") (pintype "bidirectional"))
      (node (ref "Q1") (pin "2") (pinfunction "2_2") (pintype "passive"))
    )
    (net (code "69") (name "Net-(Q3-D-Pad2)") (class "Default")
      (node (ref "Q3") (pin "2") (pinfunction "D_2") (pintype "passive"))
      (node (ref "VALVE+PROXSW") (pin "2") (pinfunction "2_2") (pintype "passive"))
    )
    (net (code "70") (name "Net-(R13-Pad2)") (class "Default")
      (node (ref "R13") (pin "2") (pinfunction "2_2") (pintype "passive"))
      (node (ref "RPI_RST") (pin "C") (pinfunction "C_C") (pintype "passive"))
    )
    (net (code "71") (name "Net-(R39-Pad2)") (class "Default")
      (node (ref "R39") (pin "2") (pinfunction "2_2") (pintype "passive"))
      (node (ref "RASPI_CONNECTOR_(TOP)") (pin "22") (pinfunction "22_22") (pintype "passive"))
    )
    (net (code "72") (name "Net-(T2A-B)") (class "Default")
      (node (ref "R46") (pin "1") (pinfunction "1_1") (pintype "passive"))
      (node (ref "T2") (pin "2") (pinfunction "B_2") (pintype "passive"))
      (node (ref "T2") (pin "5") (pinfunction "C1_5") (pintype "passive"))
    )
    (net (code "73") (name "Net-(T2A-C1)") (class "Default")
      (node (ref "RASPI_CONNECTOR_(TOP)") (pin "2") (pinfunction "2_2") (pintype "passive"))
      (node (ref "T2") (pin "8") (pinfunction "C1_8") (pintype "passive"))
    )
    (net (code "74") (name "Net-(T2B-B)") (class "Default")
      (node (ref "R47") (pin "2") (pinfunction "2_2") (pintype "passive"))
      (node (ref "T2") (pin "4") (pinfunction "B_4") (pintype "passive"))
    )
    (net (code "75") (name "Net-(U1-AIN1(+))") (class "Default")
      (node (ref "C20") (pin "1") (pinfunction "1_1") (pintype "passive"))
      (node (ref "C21") (pin "1") (pinfunction "1_1") (pintype "passive"))
      (node (ref "R17") (pin "1") (pinfunction "1_1") (pintype "passive"))
      (node (ref "U1") (pin "7") (pinfunction "AIN1(+)_7") (pintype "input"))
    )
    (net (code "76") (name "Net-(U1-AIN1(-))") (class "Default")
      (node (ref "C19") (pin "1") (pinfunction "1_1") (pintype "passive"))
      (node (ref "C21") (pin "2") (pinfunction "2_2") (pintype "passive"))
      (node (ref "R30") (pin "1") (pinfunction "1_1") (pintype "passive"))
      (node (ref "U1") (pin "8") (pinfunction "AIN1(-)_8") (pintype "input"))
    )
    (net (code "77") (name "Net-(U1-AIN2(+))") (class "Default")
      (node (ref "C22") (pin "1") (pinfunction "1_1") (pintype "passive"))
      (node (ref "C23") (pin "1") (pinfunction "1_1") (pintype "passive"))
      (node (ref "R31") (pin "1") (pinfunction "1_1") (pintype "passive"))
      (node (ref "U1") (pin "9") (pinfunction "AIN2(+)_9") (pintype "input"))
    )
    (net (code "78") (name "Net-(U1-AIN2(-))") (class "Default")
      (node (ref "C22") (pin "2") (pinfunction "2_2") (pintype "passive"))
      (node (ref "C24") (pin "1") (pinfunction "1_1") (pintype "passive"))
      (node (ref "R32") (pin "1") (pinfunction "1_1") (pintype "passive"))
      (node (ref "U1") (pin "10") (pinfunction "AIN2(-)_10") (pintype "input"))
    )
    (net (code "79") (name "Net-(U1-AIN3(+))") (class "Default")
      (node (ref "C26") (pin "1") (pinfunction "1_1") (pintype "passive"))
      (node (ref "C28") (pin "1") (pinfunction "1_1") (pintype "passive"))
      (node (ref "R33") (pin "1") (pinfunction "1_1") (pintype "passive"))
      (node (ref "U1") (pin "11") (pinfunction "AIN3(+)_11") (pintype "input"))
    )
    (net (code "80") (name "Net-(U1-AIN3(-))") (class "Default")
      (node (ref "C27") (pin "1") (pinfunction "1_1") (pintype "passive"))
      (node (ref "C28") (pin "2") (pinfunction "2_2") (pintype "passive"))
      (node (ref "R34") (pin "1") (pinfunction "1_1") (pintype "passive"))
      (node (ref "U1") (pin "12") (pinfunction "AIN3(-)_12") (pintype "input"))
    )
    (net (code "81") (name "Net-(U1-AIN4(+){slash}REFIN2(+))") (class "Default")
      (node (ref "C30") (pin "1") (pinfunction "1_1") (pintype "passive"))
      (node (ref "C32") (pin "1") (pinfunction "1_1") (pintype "passive"))
      (node (ref "R35") (pin "1") (pinfunction "1_1") (pintype "passive"))
      (node (ref "U1") (pin "17") (pinfunction "AIN4(+)/REFIN2(+)_17") (pintype "input"))
    )
    (net (code "82") (name "Net-(U1-AIN4(-){slash}REFIN2(-))") (class "Default")
      (node (ref "C31") (pin "1") (pinfunction "1_1") (pintype "passive"))
      (node (ref "C32") (pin "2") (pinfunction "2_2") (pintype "passive"))
      (node (ref "R36") (pin "1") (pinfunction "1_1") (pintype "passive"))
      (node (ref "U1") (pin "18") (pinfunction "AIN4(-)/REFIN2(-)_18") (pintype "input"))
    )
    (net (code "83") (name "Net-(U1-AIN5(+){slash}IOUT2)") (class "Default")
      (node (ref "C35") (pin "1") (pinfunction "1_1") (pintype "passive"))
      (node (ref "C36") (pin "1") (pinfunction "1_1") (pintype "passive"))
      (node (ref "R37") (pin "1") (pinfunction "1_1") (pintype "passive"))
      (node (ref "U1") (pin "15") (pinfunction "AIN5(+)/IOUT2_15") (pintype "bidirectional"))
    )
    (net (code "84") (name "Net-(U1-AIN5(-){slash}IOUT1)") (class "Default")
      (node (ref "C34") (pin "1") (pinfunction "1_1") (pintype "passive"))
      (node (ref "C36") (pin "2") (pinfunction "2_2") (pintype "passive"))
      (node (ref "R38") (pin "1") (pinfunction "1_1") (pintype "passive"))
      (node (ref "U1") (pin "16") (pinfunction "AIN5(-)/IOUT1_16") (pintype "bidirectional"))
    )
    (net (code "85") (name "unconnected-(IC1-BYPASS-Pad7)") (class "Default")
      (node (ref "IC1") (pin "7") (pinfunction "BYPASS_7") (pintype "passive"))
    )
    (net (code "86") (name "unconnected-(IC1-GAIN-Pad1)") (class "Default")
      (node (ref "IC1") (pin "1") (pinfunction "GAIN_1") (pintype "passive"))
    )
    (net (code "87") (name "unconnected-(IC1-GAIN-Pad8)") (class "Default")
      (node (ref "IC1") (pin "8") (pinfunction "GAIN_8") (pintype "passive"))
    )
    (net (code "88") (name "unconnected-(IC2-AREF-Pad29)") (class "Default")
      (node (ref "IC2") (pin "29") (pinfunction "AREF_29") (pintype "passive"))
    )
    (net (code "89") (name "unconnected-(J3-Pad2)") (class "Default")
      (node (ref "J3") (pin "2") (pinfunction "2_2") (pintype "bidirectional"))
    )
    (net (code "90") (name "unconnected-(POWR_BRD-Pad6)") (class "Default")
      (node (ref "POWR_BRD") (pin "6") (pinfunction "6_6") (pintype "passive"))
    )
    (net (code "91") (name "unconnected-(POWR_BRD-Pad8)") (class "Default")
      (node (ref "POWR_BRD") (pin "8") (pinfunction "8_8") (pintype "passive"))
    )
    (net (code "92") (name "unconnected-(POWR_BRD-Pad10)") (class "Default")
      (node (ref "POWR_BRD") (pin "10") (pinfunction "10_10") (pintype "passive"))
    )
    (net (code "93") (name "unconnected-(POWR_BRD-Pad12)") (class "Default")
      (node (ref "POWR_BRD") (pin "12") (pinfunction "12_12") (pintype "passive"))
    )
    (net (code "94") (name "unconnected-(Q2-D-Pad4)") (class "Default")
      (node (ref "Q2") (pin "4") (pinfunction "D_4") (pintype "passive"))
    )
    (net (code "95") (name "unconnected-(Q3-D-Pad4)") (class "Default")
      (node (ref "Q3") (pin "4") (pinfunction "D_4") (pintype "passive"))
    )
    (net (code "96") (name "unconnected-(RASPI_CONNECTOR_(TOP)-Pad1)") (class "Default")
      (node (ref "RASPI_CONNECTOR_(TOP)") (pin "1") (pinfunction "1_1") (pintype "passive"))
    )
    (net (code "97") (name "unconnected-(RASPI_CONNECTOR_(TOP)-Pad4)") (class "Default")
      (node (ref "RASPI_CONNECTOR_(TOP)") (pin "4") (pinfunction "4_4") (pintype "passive"))
    )
    (net (code "98") (name "unconnected-(RASPI_CONNECTOR_(TOP)-Pad7)") (class "Default")
      (node (ref "RASPI_CONNECTOR_(TOP)") (pin "7") (pinfunction "7_7") (pintype "passive"))
    )
    (net (code "99") (name "unconnected-(RASPI_CONNECTOR_(TOP)-Pad9)") (class "Default")
      (node (ref "RASPI_CONNECTOR_(TOP)") (pin "9") (pinfunction "9_9") (pintype "passive"))
    )
    (net (code "100") (name "unconnected-(RASPI_CONNECTOR_(TOP)-Pad13)") (class "Default")
      (node (ref "RASPI_CONNECTOR_(TOP)") (pin "13") (pinfunction "13_13") (pintype "passive"))
    )
    (net (code "101") (name "unconnected-(RASPI_CONNECTOR_(TOP)-Pad14)") (class "Default")
      (node (ref "RASPI_CONNECTOR_(TOP)") (pin "14") (pinfunction "14_14") (pintype "passive"))
    )
    (net (code "102") (name "unconnected-(RASPI_CONNECTOR_(TOP)-Pad15)") (class "Default")
      (node (ref "RASPI_CONNECTOR_(TOP)") (pin "15") (pinfunction "15_15") (pintype "passive"))
    )
    (net (code "103") (name "unconnected-(RASPI_CONNECTOR_(TOP)-Pad17)") (class "Default")
      (node (ref "RASPI_CONNECTOR_(TOP)") (pin "17") (pinfunction "17_17") (pintype "passive"))
    )
    (net (code "104") (name "unconnected-(RASPI_CONNECTOR_(TOP)-Pad20)") (class "Default")
      (node (ref "RASPI_CONNECTOR_(TOP)") (pin "20") (pinfunction "20_20") (pintype "passive"))
    )
    (net (code "105") (name "unconnected-(RASPI_CONNECTOR_(TOP)-Pad25)") (class "Default")
      (node (ref "RASPI_CONNECTOR_(TOP)") (pin "25") (pinfunction "25_25") (pintype "passive"))
    )
    (net (code "106") (name "unconnected-(T2A-C-Pad7)") (class "Default")
      (node (ref "T2") (pin "7") (pinfunction "C_7") (pintype "passive"))
    )
    (net (code "107") (name "unconnected-(T2B-C2-Pad6)") (class "Default")
      (node (ref "T2") (pin "6") (pinfunction "C2_6") (pintype "passive"))
    )
    (net (code "108") (name "unconnected-(U1-CLK-Pad2)") (class "Default")
      (node (ref "U1") (pin "2") (pinfunction "CLK_2") (pintype "input"))
    )
    (net (code "109") (name "unconnected-(U1-NC-Pad4)") (class "Default")
      (node (ref "U1") (pin "4") (pinfunction "NC_4") (pintype "no_connect"))
    )
  )
)
